# Viehmann_GPS_2015.net
KiCad netlist of a schematic drawn in EAGLE
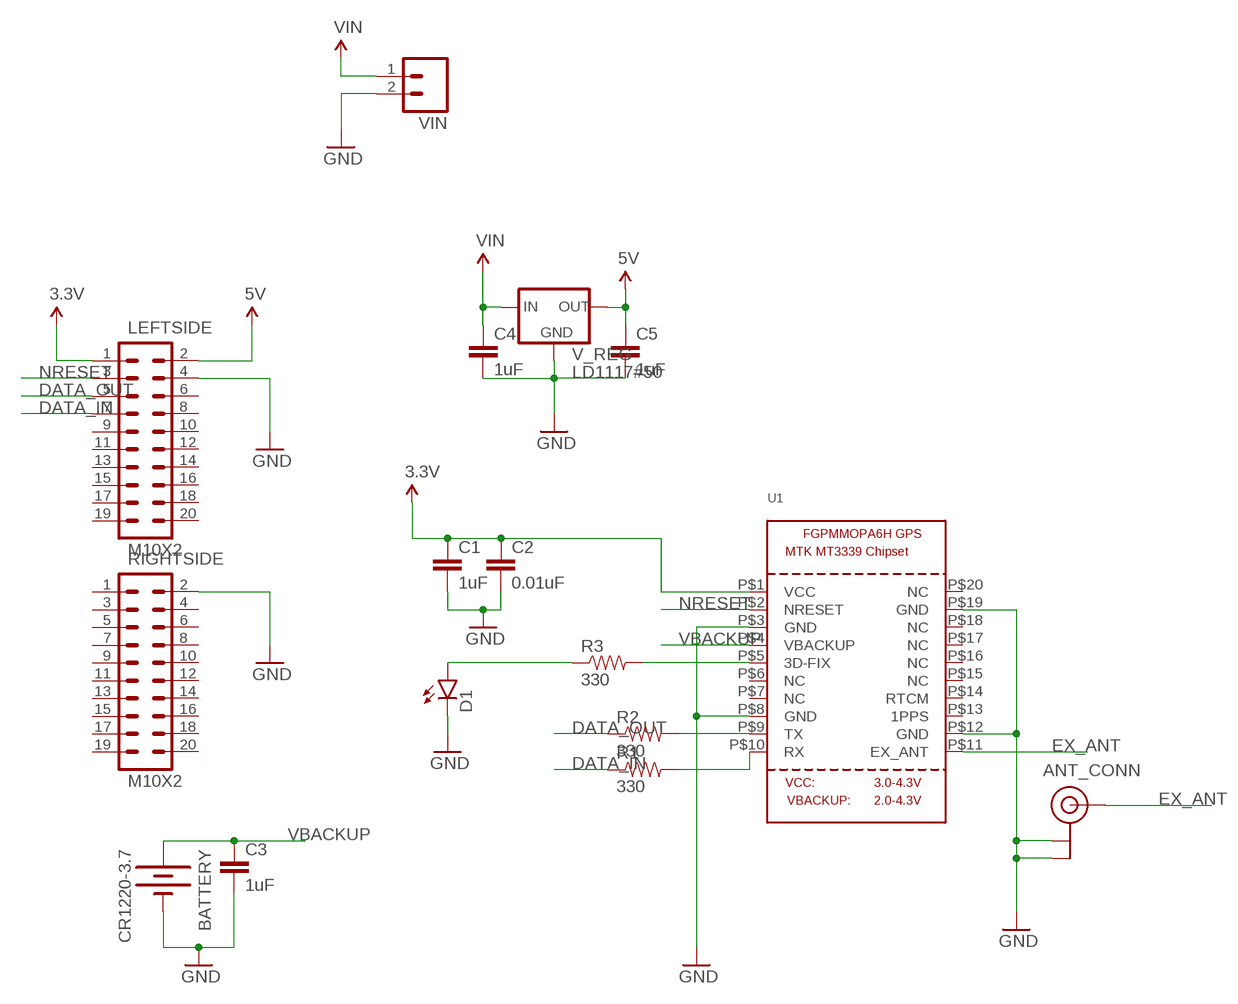
[diagram p0: schematic, sheet 1]

(export (version "E")
  (design (tool "Eeschema 10.0.6"))
  (components
    (comp (ref "ANT_CONN")
      (value "U.FL")
      (footprint "eagle-import:U.FL")
      (libsource (lib "eagle-import") (part "U.FL"))
    )
    (comp (ref "BATTERY")
      (value "CR1220-3.7")
      (footprint "eagle-import:BATTCON_12MM")
      (libsource (lib "eagle-import") (part "BATTERY12MM"))
    )
    (comp (ref "C1")
      (value "1uF")
      (footprint "eagle-import:1206")
      (libsource (lib "eagle-import") (part "CAP1206"))
    )
    (comp (ref "C2")
      (value "0.01uF")
      (footprint "eagle-import:1206")
      (libsource (lib "eagle-import") (part "CAP1206"))
    )
    (comp (ref "C3")
      (value "1uF")
      (footprint "eagle-import:1206")
      (libsource (lib "eagle-import") (part "CAP1206"))
    )
    (comp (ref "C4")
      (value "1uF")
      (footprint "eagle-import:1206")
      (libsource (lib "eagle-import") (part "CAP1206"))
    )
    (comp (ref "C5")
      (value "1uF")
      (footprint "eagle-import:1206")
      (libsource (lib "eagle-import") (part "CAP1206"))
    )
    (comp (ref "D1")
      (value "LED1206")
      (footprint "eagle-import:LED-1206")
      (libsource (lib "eagle-import") (part "LED1206"))
    )
    (comp (ref "LEFTSIDE")
      (value "M10X2")
      (footprint "eagle-import:2X10")
      (libsource (lib "eagle-import") (part "M10X2"))
    )
    (comp (ref "R1")
      (value "330")
      (footprint "eagle-import:1206")
      (libsource (lib "eagle-import") (part "RESISTOR1206"))
    )
    (comp (ref "R2")
      (value "330")
      (footprint "eagle-import:1206")
      (libsource (lib "eagle-import") (part "RESISTOR1206"))
    )
    (comp (ref "R3")
      (value "330")
      (footprint "eagle-import:1206")
      (libsource (lib "eagle-import") (part "RESISTOR1206"))
    )
    (comp (ref "RIGHTSIDE")
      (value "M10X2")
      (footprint "eagle-import:2X10")
      (libsource (lib "eagle-import") (part "M10X2"))
    )
    (comp (ref "U1")
      (value "GPS_FGPMMOPA6H")
      (footprint "eagle-import:FGPMMOPA6H")
      (libsource (lib "eagle-import") (part "GPS_FGPMMOPA6H"))
    )
    (comp (ref "VIN")
      (value "M02PTH")
      (footprint "eagle-import:1X02")
      (libsource (lib "eagle-import") (part "M02PTH"))
    )
    (comp (ref "V_REG")
      (value "LD1117#50")
      (footprint "eagle-import:SOT223")
      (libsource (lib "eagle-import") (part "V_REG_MIC2920"))
    )
  )
  (nets
    (net (code "1") (name "/DATA_IN") (class "Default")
      (node (ref "LEFTSIDE") (pin "7") (pinfunction "7_7") (pintype "passive"))
      (node (ref "R1") (pin "1") (pinfunction "1_1") (pintype "passive"))
    )
    (net (code "2") (name "/DATA_OUT") (class "Default")
      (node (ref "LEFTSIDE") (pin "5") (pinfunction "5_5") (pintype "passive"))
      (node (ref "R2") (pin "1") (pinfunction "1_1") (pintype "passive"))
    )
    (net (code "3") (name "/EX_ANT") (class "Default")
      (node (ref "ANT_CONN") (pin "P$3") (pinfunction "SIGNAL_P$3") (pintype "bidirectional"))
      (node (ref "U1") (pin "P$11") (pinfunction "EX_ANT_P$11") (pintype "bidirectional"))
    )
    (net (code "4") (name "/NRESET") (class "Default")
      (node (ref "LEFTSIDE") (pin "3") (pinfunction "3_3") (pintype "passive"))
      (node (ref "U1") (pin "P$2") (pinfunction "NRESET_P$2") (pintype "bidirectional"))
    )
    (net (code "5") (name "/VBACKUP") (class "Default")
      (node (ref "BATTERY") (pin "PWR@1") (pinfunction "+_PWR@1") (pintype "power_in"))
      (node (ref "C3") (pin "1") (pinfunction "1_1") (pintype "passive"))
      (node (ref "U1") (pin "P$4") (pinfunction "VBACKUP_P$4") (pintype "bidirectional"))
    )
    (net (code "6") (name "3.3V") (class "Default")
      (node (ref "C1") (pin "1") (pinfunction "1_1") (pintype "passive"))
      (node (ref "C2") (pin "1") (pinfunction "1_1") (pintype "passive"))
      (node (ref "LEFTSIDE") (pin "1") (pinfunction "1_1") (pintype "passive"))
      (node (ref "U1") (pin "P$1") (pinfunction "VCC_P$1") (pintype "bidirectional"))
    )
    (net (code "7") (name "5V") (class "Default")
      (node (ref "C5") (pin "1") (pinfunction "1_1") (pintype "passive"))
      (node (ref "LEFTSIDE") (pin "2") (pinfunction "2_2") (pintype "passive"))
      (node (ref "V_REG") (pin "3") (pinfunction "OUT_3") (pintype "output"))
    )
    (net (code "8") (name "GND") (class "Default")
      (node (ref "ANT_CONN") (pin "P$1") (pinfunction "GND_P$1") (pintype "bidirectional"))
      (node (ref "ANT_CONN") (pin "P$2") (pinfunction "GND_P$2") (pintype "bidirectional"))
      (node (ref "BATTERY") (pin "GND") (pinfunction "-_GND") (pintype "power_in"))
      (node (ref "C1") (pin "2") (pinfunction "2_2") (pintype "passive"))
      (node (ref "C2") (pin "2") (pinfunction "2_2") (pintype "passive"))
      (node (ref "C3") (pin "2") (pinfunction "2_2") (pintype "passive"))
      (node (ref "C4") (pin "2") (pinfunction "2_2") (pintype "passive"))
      (node (ref "C5") (pin "2") (pinfunction "2_2") (pintype "passive"))
      (node (ref "D1") (pin "C") (pinfunction "C_C") (pintype "passive"))
      (node (ref "LEFTSIDE") (pin "4") (pinfunction "4_4") (pintype "passive"))
      (node (ref "RIGHTSIDE") (pin "2") (pinfunction "2_2") (pintype "passive"))
      (node (ref "U1") (pin "P$12") (pinfunction "GND_P$12") (pintype "bidirectional"))
      (node (ref "U1") (pin "P$19") (pinfunction "GND_P$19") (pintype "bidirectional"))
      (node (ref "U1") (pin "P$3") (pinfunction "GND_P$3") (pintype "bidirectional"))
      (node (ref "U1") (pin "P$8") (pinfunction "GND_P$8") (pintype "bidirectional"))
      (node (ref "VIN") (pin "2") (pinfunction "2_2") (pintype "passive"))
      (node (ref "V_REG") (pin "2") (pinfunction "GND_2") (pintype "input"))
    )
    (net (code "9") (name "Net-(D1-PadA)") (class "Default")
      (node (ref "D1") (pin "A") (pinfunction "A_A") (pintype "passive"))
      (node (ref "R3") (pin "1") (pinfunction "1_1") (pintype "passive"))
    )
    (net (code "10") (name "Net-(U1-3D-FIX)") (class "Default")
      (node (ref "R3") (pin "2") (pinfunction "2_2") (pintype "passive"))
      (node (ref "U1") (pin "P$5") (pinfunction "3D-FIX_P$5") (pintype "bidirectional"))
    )
    (net (code "11") (name "Net-(U1-RX)") (class "Default")
      (node (ref "R1") (pin "2") (pinfunction "2_2") (pintype "passive"))
      (node (ref "U1") (pin "P$10") (pinfunction "RX_P$10") (pintype "bidirectional"))
    )
    (net (code "12") (name "Net-(U1-TX)") (class "Default")
      (node (ref "R2") (pin "2") (pinfunction "2_2") (pintype "passive"))
      (node (ref "U1") (pin "P$9") (pinfunction "TX_P$9") (pintype "bidirectional"))
    )
    (net (code "13") (name "VIN") (class "Default")
      (node (ref "C4") (pin "1") (pinfunction "1_1") (pintype "passive"))
      (node (ref "VIN") (pin "1") (pinfunction "1_1") (pintype "passive"))
      (node (ref "V_REG") (pin "1") (pinfunction "IN_1") (pintype "input"))
    )
    (net (code "14") (name "unconnected-(LEFTSIDE-Pad6)") (class "Default")
      (node (ref "LEFTSIDE") (pin "6") (pinfunction "6_6") (pintype "passive"))
    )
    (net (code "15") (name "unconnected-(LEFTSIDE-Pad8)") (class "Default")
      (node (ref "LEFTSIDE") (pin "8") (pinfunction "8_8") (pintype "passive"))
    )
    (net (code "16") (name "unconnected-(LEFTSIDE-Pad9)") (class "Default")
      (node (ref "LEFTSIDE") (pin "9") (pinfunction "9_9") (pintype "passive"))
    )
    (net (code "17") (name "unconnected-(LEFTSIDE-Pad10)") (class "Default")
      (node (ref "LEFTSIDE") (pin "10") (pinfunction "10_10") (pintype "passive"))
    )
    (net (code "18") (name "unconnected-(LEFTSIDE-Pad11)") (class "Default")
      (node (ref "LEFTSIDE") (pin "11") (pinfunction "11_11") (pintype "passive"))
    )
    (net (code "19") (name "unconnected-(LEFTSIDE-Pad12)") (class "Default")
      (node (ref "LEFTSIDE") (pin "12") (pinfunction "12_12") (pintype "passive"))
    )
    (net (code "20") (name "unconnected-(LEFTSIDE-Pad13)") (class "Default")
      (node (ref "LEFTSIDE") (pin "13") (pinfunction "13_13") (pintype "passive"))
    )
    (net (code "21") (name "unconnected-(LEFTSIDE-Pad14)") (class "Default")
      (node (ref "LEFTSIDE") (pin "14") (pinfunction "14_14") (pintype "passive"))
    )
    (net (code "22") (name "unconnected-(LEFTSIDE-Pad15)") (class "Default")
      (node (ref "LEFTSIDE") (pin "15") (pinfunction "15_15") (pintype "passive"))
    )
    (net (code "23") (name "unconnected-(LEFTSIDE-Pad16)") (class "Default")
      (node (ref "LEFTSIDE") (pin "16") (pinfunction "16_16") (pintype "passive"))
    )
    (net (code "24") (name "unconnected-(LEFTSIDE-Pad17)") (class "Default")
      (node (ref "LEFTSIDE") (pin "17") (pinfunction "17_17") (pintype "passive"))
    )
    (net (code "25") (name "unconnected-(LEFTSIDE-Pad18)") (class "Default")
      (node (ref "LEFTSIDE") (pin "18") (pinfunction "18_18") (pintype "passive"))
    )
    (net (code "26") (name "unconnected-(LEFTSIDE-Pad19)") (class "Default")
      (node (ref "LEFTSIDE") (pin "19") (pinfunction "19_19") (pintype "passive"))
    )
    (net (code "27") (name "unconnected-(LEFTSIDE-Pad20)") (class "Default")
      (node (ref "LEFTSIDE") (pin "20") (pinfunction "20_20") (pintype "passive"))
    )
    (net (code "28") (name "unconnected-(RIGHTSIDE-Pad1)") (class "Default")
      (node (ref "RIGHTSIDE") (pin "1") (pinfunction "1_1") (pintype "passive"))
    )
    (net (code "29") (name "unconnected-(RIGHTSIDE-Pad3)") (class "Default")
      (node (ref "RIGHTSIDE") (pin "3") (pinfunction "3_3") (pintype "passive"))
    )
    (net (code "30") (name "unconnected-(RIGHTSIDE-Pad4)") (class "Default")
      (node (ref "RIGHTSIDE") (pin "4") (pinfunction "4_4") (pintype "passive"))
    )
    (net (code "31") (name "unconnected-(RIGHTSIDE-Pad5)") (class "Default")
      (node (ref "RIGHTSIDE") (pin "5") (pinfunction "5_5") (pintype "passive"))
    )
    (net (code "32") (name "unconnected-(RIGHTSIDE-Pad6)") (class "Default")
      (node (ref "RIGHTSIDE") (pin "6") (pinfunction "6_6") (pintype "passive"))
    )
    (net (code "33") (name "unconnected-(RIGHTSIDE-Pad7)") (class "Default")
      (node (ref "RIGHTSIDE") (pin "7") (pinfunction "7_7") (pintype "passive"))
    )
    (net (code "34") (name "unconnected-(RIGHTSIDE-Pad8)") (class "Default")
      (node (ref "RIGHTSIDE") (pin "8") (pinfunction "8_8") (pintype "passive"))
    )
    (net (code "35") (name "unconnected-(RIGHTSIDE-Pad9)") (class "Default")
      (node (ref "RIGHTSIDE") (pin "9") (pinfunction "9_9") (pintype "passive"))
    )
    (net (code "36") (name "unconnected-(RIGHTSIDE-Pad10)") (class "Default")
      (node (ref "RIGHTSIDE") (pin "10") (pinfunction "10_10") (pintype "passive"))
    )
    (net (code "37") (name "unconnected-(RIGHTSIDE-Pad11)") (class "Default")
      (node (ref "RIGHTSIDE") (pin "11") (pinfunction "11_11") (pintype "passive"))
    )
    (net (code "38") (name "unconnected-(RIGHTSIDE-Pad12)") (class "Default")
      (node (ref "RIGHTSIDE") (pin "12") (pinfunction "12_12") (pintype "passive"))
    )
    (net (code "39") (name "unconnected-(RIGHTSIDE-Pad13)") (class "Default")
      (node (ref "RIGHTSIDE") (pin "13") (pinfunction "13_13") (pintype "passive"))
    )
    (net (code "40") (name "unconnected-(RIGHTSIDE-Pad14)") (class "Default")
      (node (ref "RIGHTSIDE") (pin "14") (pinfunction "14_14") (pintype "passive"))
    )
    (net (code "41") (name "unconnected-(RIGHTSIDE-Pad15)") (class "Default")
      (node (ref "RIGHTSIDE") (pin "15") (pinfunction "15_15") (pintype "passive"))
    )
    (net (code "42") (name "unconnected-(RIGHTSIDE-Pad16)") (class "Default")
      (node (ref "RIGHTSIDE") (pin "16") (pinfunction "16_16") (pintype "passive"))
    )
    (net (code "43") (name "unconnected-(RIGHTSIDE-Pad17)") (class "Default")
      (node (ref "RIGHTSIDE") (pin "17") (pinfunction "17_17") (pintype "passive"))
    )
    (net (code "44") (name "unconnected-(RIGHTSIDE-Pad18)") (class "Default")
      (node (ref "RIGHTSIDE") (pin "18") (pinfunction "18_18") (pintype "passive"))
    )
    (net (code "45") (name "unconnected-(RIGHTSIDE-Pad19)") (class "Default")
      (node (ref "RIGHTSIDE") (pin "19") (pinfunction "19_19") (pintype "passive"))
    )
    (net (code "46") (name "unconnected-(RIGHTSIDE-Pad20)") (class "Default")
      (node (ref "RIGHTSIDE") (pin "20") (pinfunction "20_20") (pintype "passive"))
    )
    (net (code "47") (name "unconnected-(U1-1PPS-PadP$13)") (class "Default")
      (node (ref "U1") (pin "P$13") (pinfunction "1PPS_P$13") (pintype "bidirectional"))
    )
    (net (code "48") (name "unconnected-(U1-NC-PadP$6)") (class "Default")
      (node (ref "U1") (pin "P$6") (pinfunction "NC_P$6") (pintype "bidirectional"))
    )
    (net (code "49") (name "unconnected-(U1-NC-PadP$7)") (class "Default")
      (node (ref "U1") (pin "P$7") (pinfunction "NC_P$7") (pintype "bidirectional"))
    )
    (net (code "50") (name "unconnected-(U1-NC-PadP$15)") (class "Default")
      (node (ref "U1") (pin "P$15") (pinfunction "NC_P$15") (pintype "bidirectional"))
    )
    (net (code "51") (name "unconnected-(U1-NC-PadP$16)") (class "Default")
      (node (ref "U1") (pin "P$16") (pinfunction "NC_P$16") (pintype "bidirectional"))
    )
    (net (code "52") (name "unconnected-(U1-NC-PadP$17)") (class "Default")
      (node (ref "U1") (pin "P$17") (pinfunction "NC_P$17") (pintype "bidirectional"))
    )
    (net (code "53") (name "unconnected-(U1-NC-PadP$18)") (class "Default")
      (node (ref "U1") (pin "P$18") (pinfunction "NC_P$18") (pintype "bidirectional"))
    )
    (net (code "54") (name "unconnected-(U1-NC-PadP$20)") (class "Default")
      (node (ref "U1") (pin "P$20") (pinfunction "NC_P$20") (pintype "bidirectional"))
    )
    (net (code "55") (name "unconnected-(U1-RTCM-PadP$14)") (class "Default")
      (node (ref "U1") (pin "P$14") (pinfunction "RTCM_P$14") (pintype "bidirectional"))
    )
  )
)
